# Sheet1.net
KiCad netlist of a schematic drawn in Altium Designer
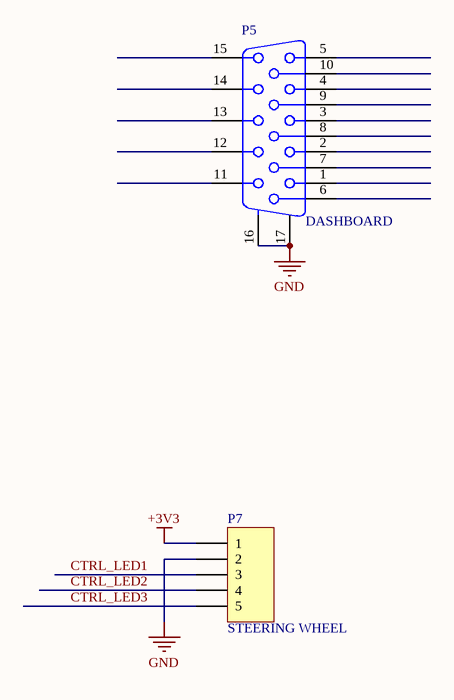
[diagram p0: Sheet1.SchDoc]

(export (version "E")
  (design (tool "Eeschema 10.0.6"))
  (components
    (comp (ref "P5")
      (value "DASHBOARD")
      (footprint "050DSUB0.762-4H15")
      (description "15-Pin, D-SUB Connector")
      (fields (field (name "PUBLISHER") "Altium Limited"))
      (libsource (lib "DataLogger") (part "D-SUB 15"))
    )
    (comp (ref "P7")
      (value "STEERING WHEEL")
      (footprint "MHDR1X5")
      (description "ST1212/P5 5 pin waterproof connector")
      (fields (field (name "PUBLISHER") "Altium Limited"))
      (libsource (lib "DataLogger") (part "MHDR1X5"))
    )
  )
  (nets
    (net (code "1") (name "+3V3") (class "Default")
      (node (ref "P7") (pin "1") (pinfunction "1_1") (pintype "passive"))
    )
    (net (code "2") (name "/CTRL_LED1") (class "Default")
      (node (ref "P7") (pin "3") (pinfunction "3_3") (pintype "passive"))
    )
    (net (code "3") (name "/CTRL_LED2") (class "Default")
      (node (ref "P7") (pin "4") (pinfunction "4_4") (pintype "passive"))
    )
    (net (code "4") (name "/CTRL_LED3") (class "Default")
      (node (ref "P7") (pin "5") (pinfunction "5_5") (pintype "passive"))
    )
    (net (code "5") (name "GND") (class "Default")
      (node (ref "P5") (pin "16") (pinfunction "MH1_16") (pintype "passive"))
      (node (ref "P5") (pin "17") (pinfunction "MH2_17") (pintype "passive"))
      (node (ref "P7") (pin "2") (pinfunction "2_2") (pintype "passive"))
    )
    (net (code "6") (name "unconnected-(P5-Pad1)") (class "Default")
      (node (ref "P5") (pin "1") (pinfunction "1_1") (pintype "passive"))
    )
    (net (code "7") (name "unconnected-(P5-Pad2)") (class "Default")
      (node (ref "P5") (pin "2") (pinfunction "2_2") (pintype "passive"))
    )
    (net (code "8") (name "unconnected-(P5-Pad3)") (class "Default")
      (node (ref "P5") (pin "3") (pinfunction "3_3") (pintype "passive"))
    )
    (net (code "9") (name "unconnected-(P5-Pad4)") (class "Default")
      (node (ref "P5") (pin "4") (pinfunction "4_4") (pintype "passive"))
    )
    (net (code "10") (name "unconnected-(P5-Pad5)") (class "Default")
      (node (ref "P5") (pin "5") (pinfunction "5_5") (pintype "passive"))
    )
    (net (code "11") (name "unconnected-(P5-Pad6)") (class "Default")
      (node (ref "P5") (pin "6") (pinfunction "6_6") (pintype "passive"))
    )
    (net (code "12") (name "unconnected-(P5-Pad7)") (class "Default")
      (node (ref "P5") (pin "7") (pinfunction "7_7") (pintype "passive"))
    )
    (net (code "13") (name "unconnected-(P5-Pad8)") (class "Default")
      (node (ref "P5") (pin "8") (pinfunction "8_8") (pintype "power_in"))
    )
    (net (code "14") (name "unconnected-(P5-Pad9)") (class "Default")
      (node (ref "P5") (pin "9") (pinfunction "9_9") (pintype "power_in"))
    )
    (net (code "15") (name "unconnected-(P5-Pad10)") (class "Default")
      (node (ref "P5") (pin "10") (pinfunction "10_10") (pintype "power_in"))
    )
    (net (code "16") (name "unconnected-(P5-Pad11)") (class "Default")
      (node (ref "P5") (pin "11") (pinfunction "11_11") (pintype "passive"))
    )
    (net (code "17") (name "unconnected-(P5-Pad12)") (class "Default")
      (node (ref "P5") (pin "12") (pinfunction "12_12") (pintype "passive"))
    )
    (net (code "18") (name "unconnected-(P5-Pad13)") (class "Default")
      (node (ref "P5") (pin "13") (pinfunction "13_13") (pintype "passive"))
    )
    (net (code "19") (name "unconnected-(P5-Pad14)") (class "Default")
      (node (ref "P5") (pin "14") (pinfunction "14_14") (pintype "passive"))
    )
    (net (code "20") (name "unconnected-(P5-Pad15)") (class "Default")
      (node (ref "P5") (pin "15") (pinfunction "15_15") (pintype "passive"))
    )
  )
)
